# DIP_1_0.net
KiCad netlist of a schematic drawn in EAGLE
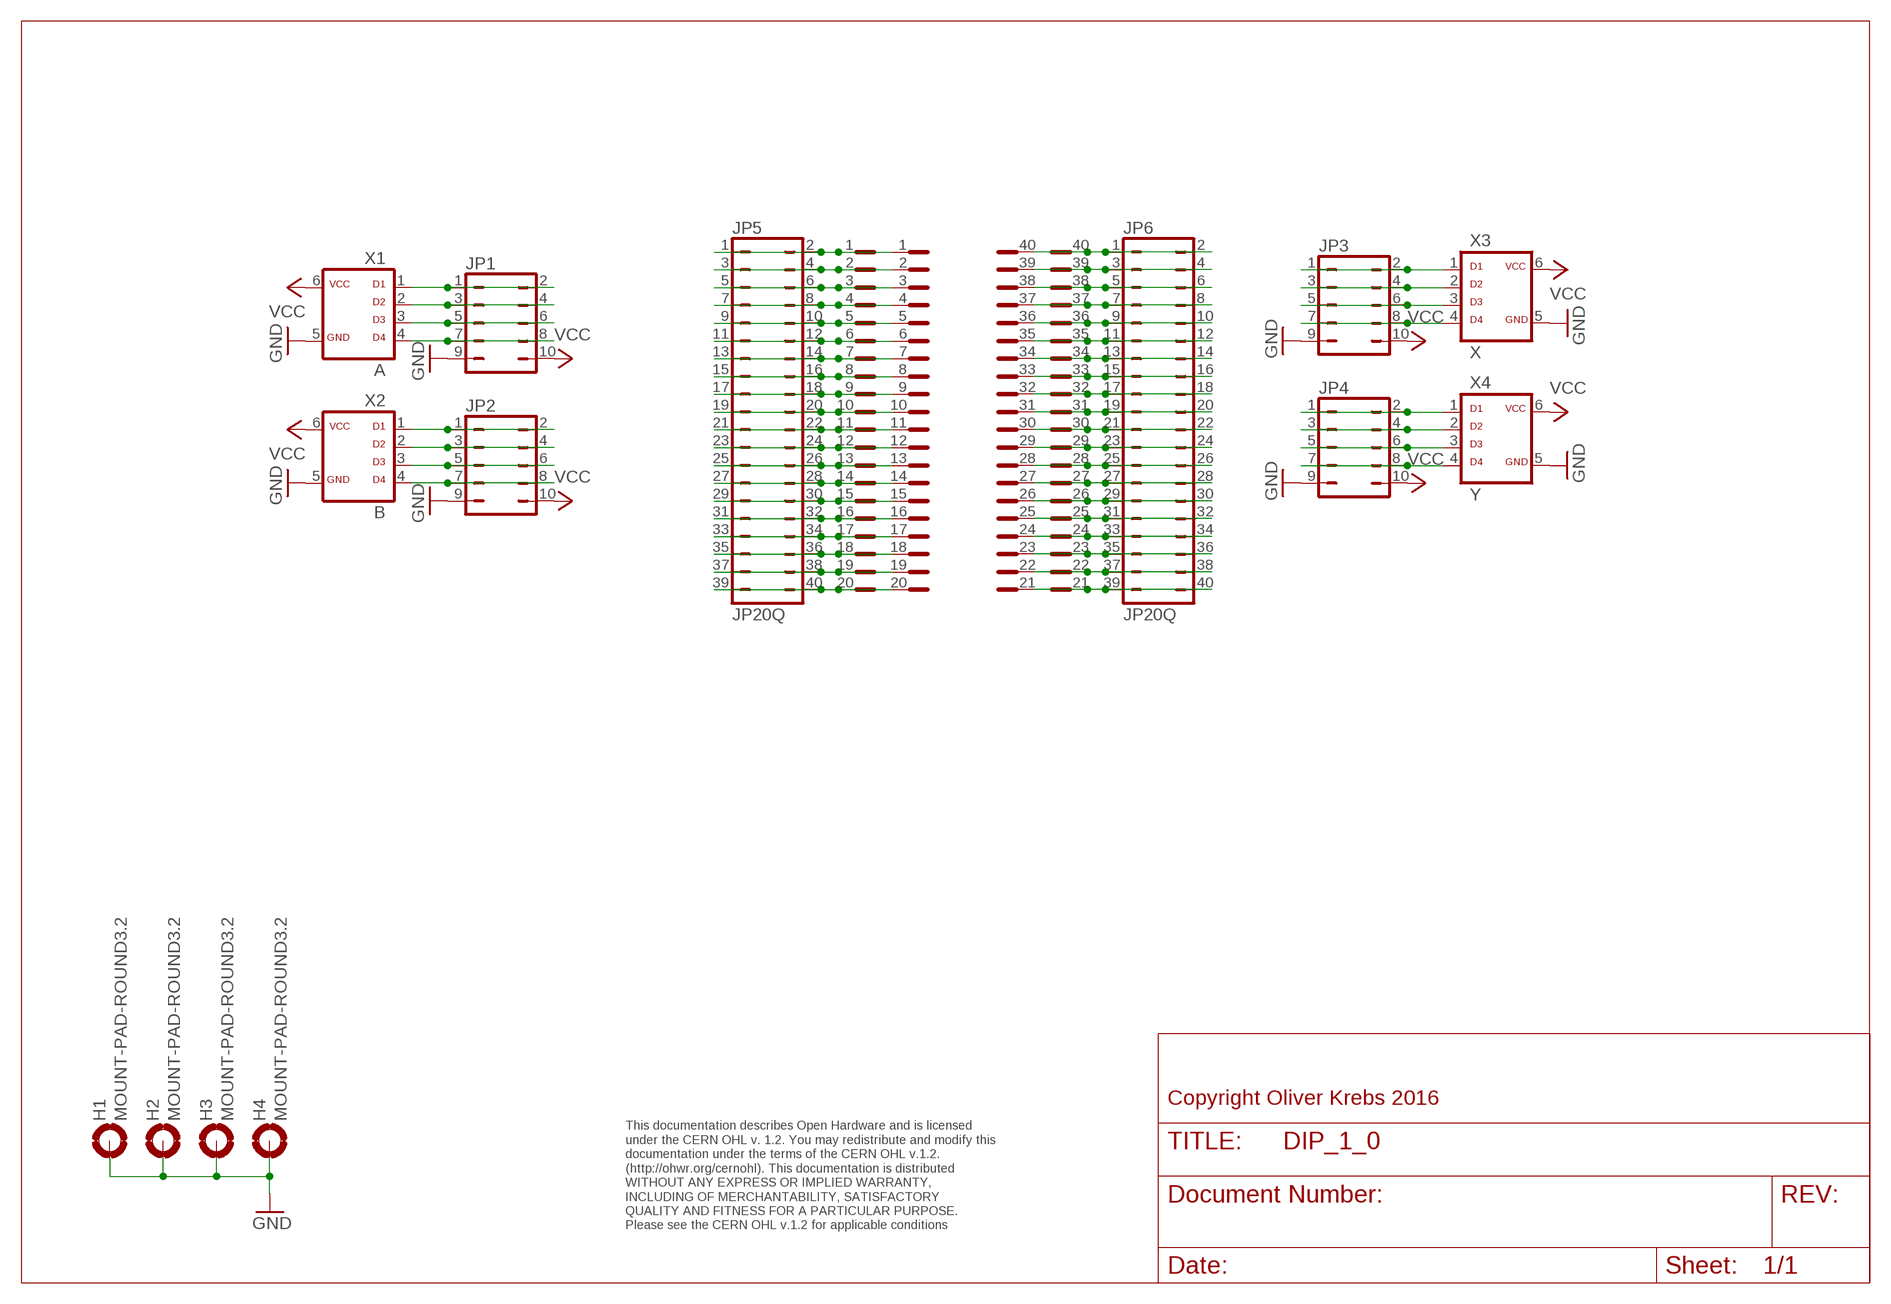
[diagram p0: schematic, sheet 1]

(export (version "E")
  (design (tool "Eeschema 10.0.6"))
  (components
    (comp (ref "H1")
      (value "MOUNT-PAD-ROUND3.2")
      (footprint "eagle-import:3,2-PAD")
      (libsource (lib "eagle-import") (part "MOUNT-PAD-ROUND3.2"))
    )
    (comp (ref "H2")
      (value "MOUNT-PAD-ROUND3.2")
      (footprint "eagle-import:3,2-PAD")
      (libsource (lib "eagle-import") (part "MOUNT-PAD-ROUND3.2"))
    )
    (comp (ref "H3")
      (value "MOUNT-PAD-ROUND3.2")
      (footprint "eagle-import:3,2-PAD")
      (libsource (lib "eagle-import") (part "MOUNT-PAD-ROUND3.2"))
    )
    (comp (ref "H4")
      (value "MOUNT-PAD-ROUND3.2")
      (footprint "eagle-import:3,2-PAD")
      (libsource (lib "eagle-import") (part "MOUNT-PAD-ROUND3.2"))
    )
    (comp (ref "JP1")
      (value "JP5Q")
      (footprint "eagle-import:JP5Q")
      (libsource (lib "eagle-import") (part "JP5Q"))
    )
    (comp (ref "JP2")
      (value "JP5Q")
      (footprint "eagle-import:JP5Q")
      (libsource (lib "eagle-import") (part "JP5Q"))
    )
    (comp (ref "JP3")
      (value "JP5Q")
      (footprint "eagle-import:JP5Q")
      (libsource (lib "eagle-import") (part "JP5Q"))
    )
    (comp (ref "JP4")
      (value "JP5Q")
      (footprint "eagle-import:JP5Q")
      (libsource (lib "eagle-import") (part "JP5Q"))
    )
    (comp (ref "JP5")
      (value "JP20Q")
      (footprint "eagle-import:JP20Q")
      (libsource (lib "eagle-import") (part "JP20Q"))
    )
    (comp (ref "JP6")
      (value "JP20Q")
      (footprint "eagle-import:JP20Q")
      (libsource (lib "eagle-import") (part "JP20Q"))
    )
    (comp (ref "X1")
      (value "A")
      (footprint "eagle-import:ML-6")
      (libsource (lib "eagle-import") (part "ML6D"))
    )
    (comp (ref "X2")
      (value "B")
      (footprint "eagle-import:ML-6")
      (libsource (lib "eagle-import") (part "ML6D"))
    )
    (comp (ref "X3")
      (value "X")
      (footprint "eagle-import:ML-6")
      (libsource (lib "eagle-import") (part "ML6D"))
    )
    (comp (ref "X4")
      (value "Y")
      (footprint "eagle-import:ML-6")
      (libsource (lib "eagle-import") (part "ML6D"))
    )
    (comp (ref "X5")
      (value "DIL40-3")
      (footprint "eagle-import:DIL40-3")
      (libsource (lib "eagle-import") (part "DIL40-3"))
    )
    (comp (ref "X6")
      (value "DIL40-6")
      (footprint "eagle-import:DIL40-6")
      (libsource (lib "eagle-import") (part "DIL40-6"))
    )
  )
  (nets
    (net (code "1") (name "GND") (class "Default")
      (node (ref "H1") (pin "B3,2") (pinfunction "MOUNT_B3,2") (pintype "passive"))
      (node (ref "H2") (pin "B3,2") (pinfunction "MOUNT_B3,2") (pintype "passive"))
      (node (ref "H3") (pin "B3,2") (pinfunction "MOUNT_B3,2") (pintype "passive"))
      (node (ref "H4") (pin "B3,2") (pinfunction "MOUNT_B3,2") (pintype "passive"))
      (node (ref "JP1") (pin "9") (pinfunction "9_9") (pintype "passive"))
      (node (ref "JP2") (pin "9") (pinfunction "9_9") (pintype "passive"))
      (node (ref "JP3") (pin "9") (pinfunction "9_9") (pintype "passive"))
      (node (ref "JP4") (pin "9") (pinfunction "9_9") (pintype "passive"))
      (node (ref "X1") (pin "5") (pinfunction "5_5") (pintype "passive"))
      (node (ref "X2") (pin "5") (pinfunction "5_5") (pintype "passive"))
      (node (ref "X3") (pin "5") (pinfunction "5_5") (pintype "passive"))
      (node (ref "X4") (pin "5") (pinfunction "5_5") (pintype "passive"))
    )
    (net (code "2") (name "Net-(JP1-Pad1)") (class "Default")
      (node (ref "JP1") (pin "1") (pinfunction "1_1") (pintype "passive"))
      (node (ref "JP1") (pin "2") (pinfunction "2_2") (pintype "passive"))
      (node (ref "X1") (pin "1") (pinfunction "1_1") (pintype "passive"))
    )
    (net (code "3") (name "Net-(JP1-Pad3)") (class "Default")
      (node (ref "JP1") (pin "3") (pinfunction "3_3") (pintype "passive"))
      (node (ref "JP1") (pin "4") (pinfunction "4_4") (pintype "passive"))
      (node (ref "X1") (pin "2") (pinfunction "2_2") (pintype "passive"))
    )
    (net (code "4") (name "Net-(JP1-Pad5)") (class "Default")
      (node (ref "JP1") (pin "5") (pinfunction "5_5") (pintype "passive"))
      (node (ref "JP1") (pin "6") (pinfunction "6_6") (pintype "passive"))
      (node (ref "X1") (pin "3") (pinfunction "3_3") (pintype "passive"))
    )
    (net (code "5") (name "Net-(JP1-Pad7)") (class "Default")
      (node (ref "JP1") (pin "7") (pinfunction "7_7") (pintype "passive"))
      (node (ref "JP1") (pin "8") (pinfunction "8_8") (pintype "passive"))
      (node (ref "X1") (pin "4") (pinfunction "4_4") (pintype "passive"))
    )
    (net (code "6") (name "Net-(JP2-Pad1)") (class "Default")
      (node (ref "JP2") (pin "1") (pinfunction "1_1") (pintype "passive"))
      (node (ref "JP2") (pin "2") (pinfunction "2_2") (pintype "passive"))
      (node (ref "X2") (pin "1") (pinfunction "1_1") (pintype "passive"))
    )
    (net (code "7") (name "Net-(JP2-Pad3)") (class "Default")
      (node (ref "JP2") (pin "3") (pinfunction "3_3") (pintype "passive"))
      (node (ref "JP2") (pin "4") (pinfunction "4_4") (pintype "passive"))
      (node (ref "X2") (pin "2") (pinfunction "2_2") (pintype "passive"))
    )
    (net (code "8") (name "Net-(JP2-Pad5)") (class "Default")
      (node (ref "JP2") (pin "5") (pinfunction "5_5") (pintype "passive"))
      (node (ref "JP2") (pin "6") (pinfunction "6_6") (pintype "passive"))
      (node (ref "X2") (pin "3") (pinfunction "3_3") (pintype "passive"))
    )
    (net (code "9") (name "Net-(JP2-Pad7)") (class "Default")
      (node (ref "JP2") (pin "7") (pinfunction "7_7") (pintype "passive"))
      (node (ref "JP2") (pin "8") (pinfunction "8_8") (pintype "passive"))
      (node (ref "X2") (pin "4") (pinfunction "4_4") (pintype "passive"))
    )
    (net (code "10") (name "Net-(JP3-Pad1)") (class "Default")
      (node (ref "JP3") (pin "1") (pinfunction "1_1") (pintype "passive"))
      (node (ref "JP3") (pin "2") (pinfunction "2_2") (pintype "passive"))
      (node (ref "X3") (pin "1") (pinfunction "1_1") (pintype "passive"))
    )
    (net (code "11") (name "Net-(JP3-Pad3)") (class "Default")
      (node (ref "JP3") (pin "3") (pinfunction "3_3") (pintype "passive"))
      (node (ref "JP3") (pin "4") (pinfunction "4_4") (pintype "passive"))
      (node (ref "X3") (pin "2") (pinfunction "2_2") (pintype "passive"))
    )
    (net (code "12") (name "Net-(JP3-Pad5)") (class "Default")
      (node (ref "JP3") (pin "5") (pinfunction "5_5") (pintype "passive"))
      (node (ref "JP3") (pin "6") (pinfunction "6_6") (pintype "passive"))
      (node (ref "X3") (pin "3") (pinfunction "3_3") (pintype "passive"))
    )
    (net (code "13") (name "Net-(JP3-Pad7)") (class "Default")
      (node (ref "JP3") (pin "7") (pinfunction "7_7") (pintype "passive"))
      (node (ref "JP3") (pin "8") (pinfunction "8_8") (pintype "passive"))
      (node (ref "X3") (pin "4") (pinfunction "4_4") (pintype "passive"))
    )
    (net (code "14") (name "Net-(JP4-Pad1)") (class "Default")
      (node (ref "JP4") (pin "1") (pinfunction "1_1") (pintype "passive"))
      (node (ref "JP4") (pin "2") (pinfunction "2_2") (pintype "passive"))
      (node (ref "X4") (pin "1") (pinfunction "1_1") (pintype "passive"))
    )
    (net (code "15") (name "Net-(JP4-Pad3)") (class "Default")
      (node (ref "JP4") (pin "3") (pinfunction "3_3") (pintype "passive"))
      (node (ref "JP4") (pin "4") (pinfunction "4_4") (pintype "passive"))
      (node (ref "X4") (pin "2") (pinfunction "2_2") (pintype "passive"))
    )
    (net (code "16") (name "Net-(JP4-Pad5)") (class "Default")
      (node (ref "JP4") (pin "5") (pinfunction "5_5") (pintype "passive"))
      (node (ref "JP4") (pin "6") (pinfunction "6_6") (pintype "passive"))
      (node (ref "X4") (pin "3") (pinfunction "3_3") (pintype "passive"))
    )
    (net (code "17") (name "Net-(JP4-Pad7)") (class "Default")
      (node (ref "JP4") (pin "7") (pinfunction "7_7") (pintype "passive"))
      (node (ref "JP4") (pin "8") (pinfunction "8_8") (pintype "passive"))
      (node (ref "X4") (pin "4") (pinfunction "4_4") (pintype "passive"))
    )
    (net (code "18") (name "Net-(X5A-P$1)") (class "Default")
      (node (ref "JP5") (pin "1") (pinfunction "1_1") (pintype "passive"))
      (node (ref "JP5") (pin "2") (pinfunction "2_2") (pintype "passive"))
      (node (ref "X5") (pin "1") (pinfunction "P$1_1") (pintype "bidirectional"))
      (node (ref "X6") (pin "1") (pinfunction "P$1_1") (pintype "bidirectional"))
    )
    (net (code "19") (name "Net-(X5A-P$2)") (class "Default")
      (node (ref "JP5") (pin "3") (pinfunction "3_3") (pintype "passive"))
      (node (ref "JP5") (pin "4") (pinfunction "4_4") (pintype "passive"))
      (node (ref "X5") (pin "2") (pinfunction "P$2_2") (pintype "bidirectional"))
      (node (ref "X6") (pin "2") (pinfunction "P$2_2") (pintype "bidirectional"))
    )
    (net (code "20") (name "Net-(X5A-P$3)") (class "Default")
      (node (ref "JP5") (pin "5") (pinfunction "5_5") (pintype "passive"))
      (node (ref "JP5") (pin "6") (pinfunction "6_6") (pintype "passive"))
      (node (ref "X5") (pin "3") (pinfunction "P$3_3") (pintype "bidirectional"))
      (node (ref "X6") (pin "3") (pinfunction "P$3_3") (pintype "bidirectional"))
    )
    (net (code "21") (name "Net-(X5A-P$4)") (class "Default")
      (node (ref "JP5") (pin "7") (pinfunction "7_7") (pintype "passive"))
      (node (ref "JP5") (pin "8") (pinfunction "8_8") (pintype "passive"))
      (node (ref "X5") (pin "4") (pinfunction "P$4_4") (pintype "bidirectional"))
      (node (ref "X6") (pin "4") (pinfunction "P$4_4") (pintype "bidirectional"))
    )
    (net (code "22") (name "Net-(X5A-P$5)") (class "Default")
      (node (ref "JP5") (pin "10") (pinfunction "10_10") (pintype "passive"))
      (node (ref "JP5") (pin "9") (pinfunction "9_9") (pintype "passive"))
      (node (ref "X5") (pin "5") (pinfunction "P$5_5") (pintype "bidirectional"))
      (node (ref "X6") (pin "5") (pinfunction "P$5_5") (pintype "bidirectional"))
    )
    (net (code "23") (name "Net-(X5A-P$6)") (class "Default")
      (node (ref "JP5") (pin "11") (pinfunction "11_11") (pintype "passive"))
      (node (ref "JP5") (pin "12") (pinfunction "12_12") (pintype "passive"))
      (node (ref "X5") (pin "6") (pinfunction "P$6_6") (pintype "bidirectional"))
      (node (ref "X6") (pin "6") (pinfunction "P$6_6") (pintype "bidirectional"))
    )
    (net (code "24") (name "Net-(X5A-P$7)") (class "Default")
      (node (ref "JP5") (pin "13") (pinfunction "13_13") (pintype "passive"))
      (node (ref "JP5") (pin "14") (pinfunction "14_14") (pintype "passive"))
      (node (ref "X5") (pin "7") (pinfunction "P$7_7") (pintype "bidirectional"))
      (node (ref "X6") (pin "7") (pinfunction "P$7_7") (pintype "bidirectional"))
    )
    (net (code "25") (name "Net-(X5A-P$8)") (class "Default")
      (node (ref "JP5") (pin "15") (pinfunction "15_15") (pintype "passive"))
      (node (ref "JP5") (pin "16") (pinfunction "16_16") (pintype "passive"))
      (node (ref "X5") (pin "8") (pinfunction "P$8_8") (pintype "bidirectional"))
      (node (ref "X6") (pin "8") (pinfunction "P$8_8") (pintype "bidirectional"))
    )
    (net (code "26") (name "Net-(X5A-P$9)") (class "Default")
      (node (ref "JP5") (pin "17") (pinfunction "17_17") (pintype "passive"))
      (node (ref "JP5") (pin "18") (pinfunction "18_18") (pintype "passive"))
      (node (ref "X5") (pin "9") (pinfunction "P$9_9") (pintype "bidirectional"))
      (node (ref "X6") (pin "9") (pinfunction "P$9_9") (pintype "bidirectional"))
    )
    (net (code "27") (name "Net-(X5A-P$10)") (class "Default")
      (node (ref "JP5") (pin "19") (pinfunction "19_19") (pintype "passive"))
      (node (ref "JP5") (pin "20") (pinfunction "20_20") (pintype "passive"))
      (node (ref "X5") (pin "10") (pinfunction "P$10_10") (pintype "bidirectional"))
      (node (ref "X6") (pin "10") (pinfunction "P$10_10") (pintype "bidirectional"))
    )
    (net (code "28") (name "Net-(X5A-P$11)") (class "Default")
      (node (ref "JP5") (pin "21") (pinfunction "21_21") (pintype "passive"))
      (node (ref "JP5") (pin "22") (pinfunction "22_22") (pintype "passive"))
      (node (ref "X5") (pin "11") (pinfunction "P$11_11") (pintype "bidirectional"))
      (node (ref "X6") (pin "11") (pinfunction "P$11_11") (pintype "bidirectional"))
    )
    (net (code "29") (name "Net-(X5A-P$12)") (class "Default")
      (node (ref "JP5") (pin "23") (pinfunction "23_23") (pintype "passive"))
      (node (ref "JP5") (pin "24") (pinfunction "24_24") (pintype "passive"))
      (node (ref "X5") (pin "12") (pinfunction "P$12_12") (pintype "bidirectional"))
      (node (ref "X6") (pin "12") (pinfunction "P$12_12") (pintype "bidirectional"))
    )
    (net (code "30") (name "Net-(X5A-P$13)") (class "Default")
      (node (ref "JP5") (pin "25") (pinfunction "25_25") (pintype "passive"))
      (node (ref "JP5") (pin "26") (pinfunction "26_26") (pintype "passive"))
      (node (ref "X5") (pin "13") (pinfunction "P$13_13") (pintype "bidirectional"))
      (node (ref "X6") (pin "13") (pinfunction "P$13_13") (pintype "bidirectional"))
    )
    (net (code "31") (name "Net-(X5A-P$14)") (class "Default")
      (node (ref "JP5") (pin "27") (pinfunction "27_27") (pintype "passive"))
      (node (ref "JP5") (pin "28") (pinfunction "28_28") (pintype "passive"))
      (node (ref "X5") (pin "14") (pinfunction "P$14_14") (pintype "bidirectional"))
      (node (ref "X6") (pin "14") (pinfunction "P$14_14") (pintype "bidirectional"))
    )
    (net (code "32") (name "Net-(X5A-P$15)") (class "Default")
      (node (ref "JP5") (pin "29") (pinfunction "29_29") (pintype "passive"))
      (node (ref "JP5") (pin "30") (pinfunction "30_30") (pintype "passive"))
      (node (ref "X5") (pin "15") (pinfunction "P$15_15") (pintype "bidirectional"))
      (node (ref "X6") (pin "15") (pinfunction "P$15_15") (pintype "bidirectional"))
    )
    (net (code "33") (name "Net-(X5A-P$16)") (class "Default")
      (node (ref "JP5") (pin "31") (pinfunction "31_31") (pintype "passive"))
      (node (ref "JP5") (pin "32") (pinfunction "32_32") (pintype "passive"))
      (node (ref "X5") (pin "16") (pinfunction "P$16_16") (pintype "bidirectional"))
      (node (ref "X6") (pin "16") (pinfunction "P$16_16") (pintype "bidirectional"))
    )
    (net (code "34") (name "Net-(X5A-P$17)") (class "Default")
      (node (ref "JP5") (pin "33") (pinfunction "33_33") (pintype "passive"))
      (node (ref "JP5") (pin "34") (pinfunction "34_34") (pintype "passive"))
      (node (ref "X5") (pin "17") (pinfunction "P$17_17") (pintype "bidirectional"))
      (node (ref "X6") (pin "17") (pinfunction "P$17_17") (pintype "bidirectional"))
    )
    (net (code "35") (name "Net-(X5A-P$18)") (class "Default")
      (node (ref "JP5") (pin "35") (pinfunction "35_35") (pintype "passive"))
      (node (ref "JP5") (pin "36") (pinfunction "36_36") (pintype "passive"))
      (node (ref "X5") (pin "18") (pinfunction "P$18_18") (pintype "bidirectional"))
      (node (ref "X6") (pin "18") (pinfunction "P$18_18") (pintype "bidirectional"))
    )
    (net (code "36") (name "Net-(X5A-P$19)") (class "Default")
      (node (ref "JP5") (pin "37") (pinfunction "37_37") (pintype "passive"))
      (node (ref "JP5") (pin "38") (pinfunction "38_38") (pintype "passive"))
      (node (ref "X5") (pin "19") (pinfunction "P$19_19") (pintype "bidirectional"))
      (node (ref "X6") (pin "19") (pinfunction "P$19_19") (pintype "bidirectional"))
    )
    (net (code "37") (name "Net-(X5A-P$20)") (class "Default")
      (node (ref "JP5") (pin "39") (pinfunction "39_39") (pintype "passive"))
      (node (ref "JP5") (pin "40") (pinfunction "40_40") (pintype "passive"))
      (node (ref "X5") (pin "20") (pinfunction "P$20_20") (pintype "bidirectional"))
      (node (ref "X6") (pin "20") (pinfunction "P$20_20") (pintype "bidirectional"))
    )
    (net (code "38") (name "Net-(X5B-P$1)") (class "Default")
      (node (ref "JP6") (pin "1") (pinfunction "1_1") (pintype "passive"))
      (node (ref "JP6") (pin "2") (pinfunction "2_2") (pintype "passive"))
      (node (ref "X5") (pin "40") (pinfunction "P$1_40") (pintype "bidirectional"))
      (node (ref "X6") (pin "40") (pinfunction "P$1_40") (pintype "bidirectional"))
    )
    (net (code "39") (name "Net-(X5B-P$2)") (class "Default")
      (node (ref "JP6") (pin "3") (pinfunction "3_3") (pintype "passive"))
      (node (ref "JP6") (pin "4") (pinfunction "4_4") (pintype "passive"))
      (node (ref "X5") (pin "39") (pinfunction "P$2_39") (pintype "bidirectional"))
      (node (ref "X6") (pin "39") (pinfunction "P$2_39") (pintype "bidirectional"))
    )
    (net (code "40") (name "Net-(X5B-P$3)") (class "Default")
      (node (ref "JP6") (pin "5") (pinfunction "5_5") (pintype "passive"))
      (node (ref "JP6") (pin "6") (pinfunction "6_6") (pintype "passive"))
      (node (ref "X5") (pin "38") (pinfunction "P$3_38") (pintype "bidirectional"))
      (node (ref "X6") (pin "38") (pinfunction "P$3_38") (pintype "bidirectional"))
    )
    (net (code "41") (name "Net-(X5B-P$4)") (class "Default")
      (node (ref "JP6") (pin "7") (pinfunction "7_7") (pintype "passive"))
      (node (ref "JP6") (pin "8") (pinfunction "8_8") (pintype "passive"))
      (node (ref "X5") (pin "37") (pinfunction "P$4_37") (pintype "bidirectional"))
      (node (ref "X6") (pin "37") (pinfunction "P$4_37") (pintype "bidirectional"))
    )
    (net (code "42") (name "Net-(X5B-P$5)") (class "Default")
      (node (ref "JP6") (pin "10") (pinfunction "10_10") (pintype "passive"))
      (node (ref "JP6") (pin "9") (pinfunction "9_9") (pintype "passive"))
      (node (ref "X5") (pin "36") (pinfunction "P$5_36") (pintype "bidirectional"))
      (node (ref "X6") (pin "36") (pinfunction "P$5_36") (pintype "bidirectional"))
    )
    (net (code "43") (name "Net-(X5B-P$6)") (class "Default")
      (node (ref "JP6") (pin "11") (pinfunction "11_11") (pintype "passive"))
      (node (ref "JP6") (pin "12") (pinfunction "12_12") (pintype "passive"))
      (node (ref "X5") (pin "35") (pinfunction "P$6_35") (pintype "bidirectional"))
      (node (ref "X6") (pin "35") (pinfunction "P$6_35") (pintype "bidirectional"))
    )
    (net (code "44") (name "Net-(X5B-P$7)") (class "Default")
      (node (ref "JP6") (pin "13") (pinfunction "13_13") (pintype "passive"))
      (node (ref "JP6") (pin "14") (pinfunction "14_14") (pintype "passive"))
      (node (ref "X5") (pin "34") (pinfunction "P$7_34") (pintype "bidirectional"))
      (node (ref "X6") (pin "34") (pinfunction "P$7_34") (pintype "bidirectional"))
    )
    (net (code "45") (name "Net-(X5B-P$8)") (class "Default")
      (node (ref "JP6") (pin "15") (pinfunction "15_15") (pintype "passive"))
      (node (ref "JP6") (pin "16") (pinfunction "16_16") (pintype "passive"))
      (node (ref "X5") (pin "33") (pinfunction "P$8_33") (pintype "bidirectional"))
      (node (ref "X6") (pin "33") (pinfunction "P$8_33") (pintype "bidirectional"))
    )
    (net (code "46") (name "Net-(X5B-P$9)") (class "Default")
      (node (ref "JP6") (pin "17") (pinfunction "17_17") (pintype "passive"))
      (node (ref "JP6") (pin "18") (pinfunction "18_18") (pintype "passive"))
      (node (ref "X5") (pin "32") (pinfunction "P$9_32") (pintype "bidirectional"))
      (node (ref "X6") (pin "32") (pinfunction "P$9_32") (pintype "bidirectional"))
    )
    (net (code "47") (name "Net-(X5B-P$10)") (class "Default")
      (node (ref "JP6") (pin "19") (pinfunction "19_19") (pintype "passive"))
      (node (ref "JP6") (pin "20") (pinfunction "20_20") (pintype "passive"))
      (node (ref "X5") (pin "31") (pinfunction "P$10_31") (pintype "bidirectional"))
      (node (ref "X6") (pin "31") (pinfunction "P$10_31") (pintype "bidirectional"))
    )
    (net (code "48") (name "Net-(X5B-P$11)") (class "Default")
      (node (ref "JP6") (pin "21") (pinfunction "21_21") (pintype "passive"))
      (node (ref "JP6") (pin "22") (pinfunction "22_22") (pintype "passive"))
      (node (ref "X5") (pin "30") (pinfunction "P$11_30") (pintype "bidirectional"))
      (node (ref "X6") (pin "30") (pinfunction "P$11_30") (pintype "bidirectional"))
    )
    (net (code "49") (name "Net-(X5B-P$12)") (class "Default")
      (node (ref "JP6") (pin "23") (pinfunction "23_23") (pintype "passive"))
      (node (ref "JP6") (pin "24") (pinfunction "24_24") (pintype "passive"))
      (node (ref "X5") (pin "29") (pinfunction "P$12_29") (pintype "bidirectional"))
      (node (ref "X6") (pin "29") (pinfunction "P$12_29") (pintype "bidirectional"))
    )
    (net (code "50") (name "Net-(X5B-P$13)") (class "Default")
      (node (ref "JP6") (pin "25") (pinfunction "25_25") (pintype "passive"))
      (node (ref "JP6") (pin "26") (pinfunction "26_26") (pintype "passive"))
      (node (ref "X5") (pin "28") (pinfunction "P$13_28") (pintype "bidirectional"))
      (node (ref "X6") (pin "28") (pinfunction "P$13_28") (pintype "bidirectional"))
    )
    (net (code "51") (name "Net-(X5B-P$14)") (class "Default")
      (node (ref "JP6") (pin "27") (pinfunction "27_27") (pintype "passive"))
      (node (ref "JP6") (pin "28") (pinfunction "28_28") (pintype "passive"))
      (node (ref "X5") (pin "27") (pinfunction "P$14_27") (pintype "bidirectional"))
      (node (ref "X6") (pin "27") (pinfunction "P$14_27") (pintype "bidirectional"))
    )
    (net (code "52") (name "Net-(X5B-P$15)") (class "Default")
      (node (ref "JP6") (pin "29") (pinfunction "29_29") (pintype "passive"))
      (node (ref "JP6") (pin "30") (pinfunction "30_30") (pintype "passive"))
      (node (ref "X5") (pin "26") (pinfunction "P$15_26") (pintype "bidirectional"))
      (node (ref "X6") (pin "26") (pinfunction "P$15_26") (pintype "bidirectional"))
    )
    (net (code "53") (name "Net-(X5B-P$16)") (class "Default")
      (node (ref "JP6") (pin "31") (pinfunction "31_31") (pintype "passive"))
      (node (ref "JP6") (pin "32") (pinfunction "32_32") (pintype "passive"))
      (node (ref "X5") (pin "25") (pinfunction "P$16_25") (pintype "bidirectional"))
      (node (ref "X6") (pin "25") (pinfunction "P$16_25") (pintype "bidirectional"))
    )
    (net (code "54") (name "Net-(X5B-P$17)") (class "Default")
      (node (ref "JP6") (pin "33") (pinfunction "33_33") (pintype "passive"))
      (node (ref "JP6") (pin "34") (pinfunction "34_34") (pintype "passive"))
      (node (ref "X5") (pin "24") (pinfunction "P$17_24") (pintype "bidirectional"))
      (node (ref "X6") (pin "24") (pinfunction "P$17_24") (pintype "bidirectional"))
    )
    (net (code "55") (name "Net-(X5B-P$18)") (class "Default")
      (node (ref "JP6") (pin "35") (pinfunction "35_35") (pintype "passive"))
      (node (ref "JP6") (pin "36") (pinfunction "36_36") (pintype "passive"))
      (node (ref "X5") (pin "23") (pinfunction "P$18_23") (pintype "bidirectional"))
      (node (ref "X6") (pin "23") (pinfunction "P$18_23") (pintype "bidirectional"))
    )
    (net (code "56") (name "Net-(X5B-P$19)") (class "Default")
      (node (ref "JP6") (pin "37") (pinfunction "37_37") (pintype "passive"))
      (node (ref "JP6") (pin "38") (pinfunction "38_38") (pintype "passive"))
      (node (ref "X5") (pin "22") (pinfunction "P$19_22") (pintype "bidirectional"))
      (node (ref "X6") (pin "22") (pinfunction "P$19_22") (pintype "bidirectional"))
    )
    (net (code "57") (name "Net-(X5B-P$20)") (class "Default")
      (node (ref "JP6") (pin "39") (pinfunction "39_39") (pintype "passive"))
      (node (ref "JP6") (pin "40") (pinfunction "40_40") (pintype "passive"))
      (node (ref "X5") (pin "21") (pinfunction "P$20_21") (pintype "bidirectional"))
      (node (ref "X6") (pin "21") (pinfunction "P$20_21") (pintype "bidirectional"))
    )
    (net (code "58") (name "VCC") (class "Default")
      (node (ref "JP1") (pin "10") (pinfunction "10_10") (pintype "passive"))
      (node (ref "JP2") (pin "10") (pinfunction "10_10") (pintype "passive"))
      (node (ref "JP3") (pin "10") (pinfunction "10_10") (pintype "passive"))
      (node (ref "JP4") (pin "10") (pinfunction "10_10") (pintype "passive"))
      (node (ref "X1") (pin "6") (pinfunction "6_6") (pintype "passive"))
      (node (ref "X2") (pin "6") (pinfunction "6_6") (pintype "passive"))
      (node (ref "X3") (pin "6") (pinfunction "6_6") (pintype "passive"))
      (node (ref "X4") (pin "6") (pinfunction "6_6") (pintype "passive"))
    )
  )
)
